# LED_Module.net
KiCad netlist of a schematic drawn in EAGLE
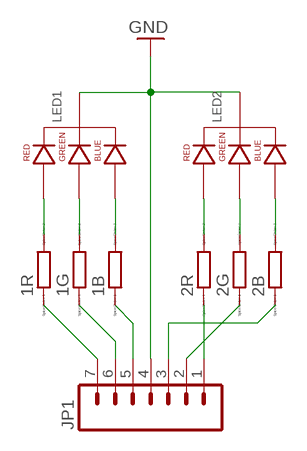
[diagram p0: schematic, sheet 1]

(export (version "E")
  (design (tool "Eeschema 10.0.6"))
  (components
    (comp (ref "1B")
      (value "RR0603")
      (footprint "eagle-import:R0603")
      (libsource (lib "eagle-import") (part "RR0603"))
    )
    (comp (ref "1G")
      (value "RR0603")
      (footprint "eagle-import:R0603")
      (libsource (lib "eagle-import") (part "RR0603"))
    )
    (comp (ref "1R")
      (value "RR0603")
      (footprint "eagle-import:R0603")
      (libsource (lib "eagle-import") (part "RR0603"))
    )
    (comp (ref "2B")
      (value "RR0603")
      (footprint "eagle-import:R0603")
      (libsource (lib "eagle-import") (part "RR0603"))
    )
    (comp (ref "2G")
      (value "RR0603")
      (footprint "eagle-import:R0603")
      (libsource (lib "eagle-import") (part "RR0603"))
    )
    (comp (ref "2R")
      (value "RR0603")
      (footprint "eagle-import:R0603")
      (libsource (lib "eagle-import") (part "RR0603"))
    )
    (comp (ref "JP1")
      (value "M07")
      (footprint "eagle-import:1X07")
      (libsource (lib "eagle-import") (part "M07"))
    )
    (comp (ref "LED1")
      (value "LED-RGB-CC-THRUDIFFUSE")
      (footprint "eagle-import:LED-RGB-THRU")
      (libsource (lib "eagle-import") (part "LED-RGB-CC-THRUDIFFUSE"))
    )
    (comp (ref "LED2")
      (value "LED-RGB-CC-THRUDIFFUSE")
      (footprint "eagle-import:LED-RGB-THRU")
      (libsource (lib "eagle-import") (part "LED-RGB-CC-THRUDIFFUSE"))
    )
  )
  (nets
    (net (code "1") (name "GND") (class "Default")
      (node (ref "JP1") (pin "4") (pinfunction "4_4") (pintype "passive"))
      (node (ref "LED1") (pin "2") (pinfunction "CATHODE_2") (pintype "bidirectional"))
      (node (ref "LED2") (pin "2") (pinfunction "CATHODE_2") (pintype "bidirectional"))
    )
    (net (code "2") (name "Net-(1B-Pad1)") (class "Default")
      (node (ref "1B") (pin "1") (pinfunction "1_1") (pintype "passive"))
      (node (ref "JP1") (pin "5") (pinfunction "5_5") (pintype "passive"))
    )
    (net (code "3") (name "Net-(1G-Pad1)") (class "Default")
      (node (ref "1G") (pin "1") (pinfunction "1_1") (pintype "passive"))
      (node (ref "JP1") (pin "6") (pinfunction "6_6") (pintype "passive"))
    )
    (net (code "4") (name "Net-(1R-Pad1)") (class "Default")
      (node (ref "1R") (pin "1") (pinfunction "1_1") (pintype "passive"))
      (node (ref "JP1") (pin "7") (pinfunction "7_7") (pintype "passive"))
    )
    (net (code "5") (name "Net-(2B-Pad1)") (class "Default")
      (node (ref "2B") (pin "1") (pinfunction "1_1") (pintype "passive"))
      (node (ref "JP1") (pin "3") (pinfunction "3_3") (pintype "passive"))
    )
    (net (code "6") (name "Net-(2G-Pad1)") (class "Default")
      (node (ref "2G") (pin "1") (pinfunction "1_1") (pintype "passive"))
      (node (ref "JP1") (pin "2") (pinfunction "2_2") (pintype "passive"))
    )
    (net (code "7") (name "Net-(2R-Pad1)") (class "Default")
      (node (ref "2R") (pin "1") (pinfunction "1_1") (pintype "passive"))
      (node (ref "JP1") (pin "1") (pinfunction "1_1") (pintype "passive"))
    )
    (net (code "8") (name "Net-(LED1-BLUE_CATHODE)") (class "Default")
      (node (ref "1B") (pin "2") (pinfunction "2_2") (pintype "passive"))
      (node (ref "LED1") (pin "4") (pinfunction "BLUE_CATHODE_4") (pintype "bidirectional"))
    )
    (net (code "9") (name "Net-(LED1-GREEN_CATHODE)") (class "Default")
      (node (ref "1G") (pin "2") (pinfunction "2_2") (pintype "passive"))
      (node (ref "LED1") (pin "3") (pinfunction "GREEN_CATHODE_3") (pintype "bidirectional"))
    )
    (net (code "10") (name "Net-(LED1-RED_CATHODE)") (class "Default")
      (node (ref "1R") (pin "2") (pinfunction "2_2") (pintype "passive"))
      (node (ref "LED1") (pin "1") (pinfunction "RED_CATHODE_1") (pintype "bidirectional"))
    )
    (net (code "11") (name "Net-(LED2-BLUE_CATHODE)") (class "Default")
      (node (ref "2B") (pin "2") (pinfunction "2_2") (pintype "passive"))
      (node (ref "LED2") (pin "4") (pinfunction "BLUE_CATHODE_4") (pintype "bidirectional"))
    )
    (net (code "12") (name "Net-(LED2-GREEN_CATHODE)") (class "Default")
      (node (ref "2G") (pin "2") (pinfunction "2_2") (pintype "passive"))
      (node (ref "LED2") (pin "3") (pinfunction "GREEN_CATHODE_3") (pintype "bidirectional"))
    )
    (net (code "13") (name "Net-(LED2-RED_CATHODE)") (class "Default")
      (node (ref "2R") (pin "2") (pinfunction "2_2") (pintype "passive"))
      (node (ref "LED2") (pin "1") (pinfunction "RED_CATHODE_1") (pintype "bidirectional"))
    )
  )
)
